# rev_1-_projecto.net
KiCad netlist of a schematic drawn in EasyEDA
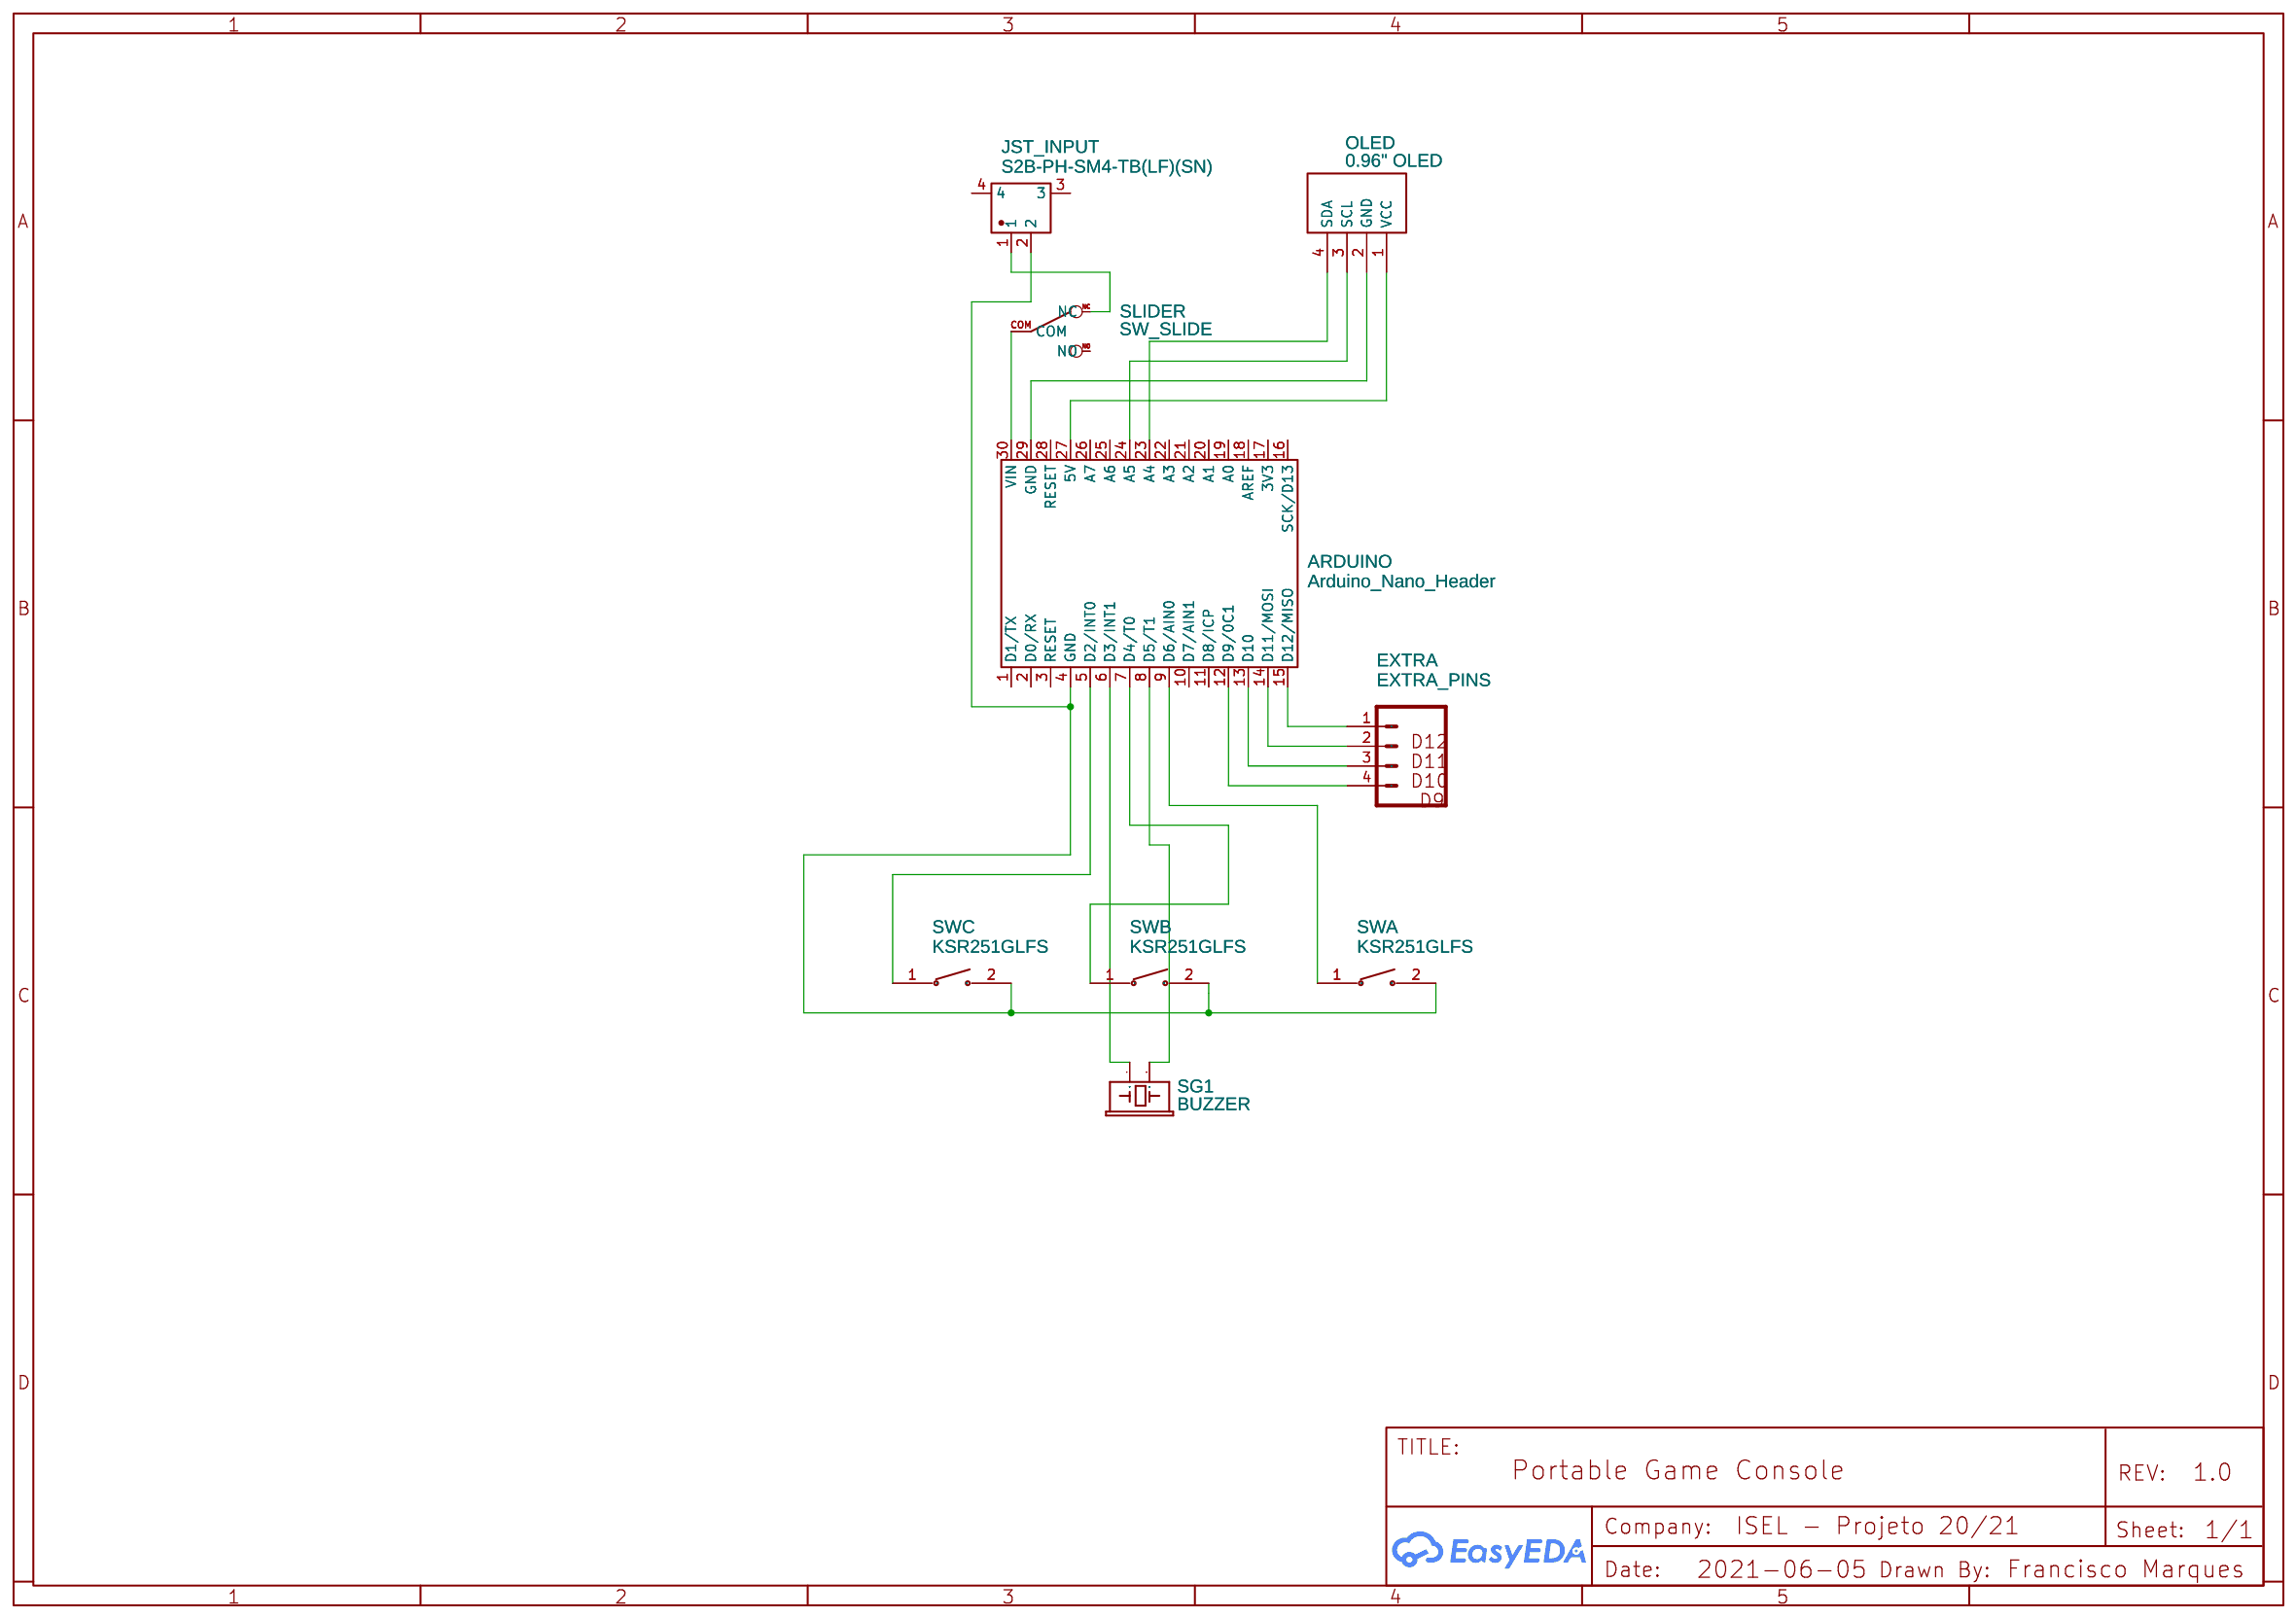
[diagram p0: schematic sheet]

(export (version "E")
  (design (tool "Eeschema 10.0.6"))
  (components
    (comp (ref "ARDUINO") (value "Arduino_Nano_Header") (libsource (lib "") (part "Arduino_Nano_Header")))
    (comp (ref "EXTRA") (value "EXTRA_PINS") (libsource (lib "") (part "EXTRA_PINS")))
    (comp (ref "JST_INPUT")
      (value "S2B-PH-SM4-TB(LF)(SN)")
      (fields (field (name "BOM_Supplier Part") "C295747"))
      (libsource (lib "") (part "S2B-PH-SM4-TB(LF)(SN)"))
    )
    (comp (ref "OLED") (value "0.96\" OLED") (libsource (lib "") (part "0.96{dblquote} OLED")))
    (comp (ref "SG1") (value "BUZZER") (libsource (lib "") (part "BUZZER")))
    (comp (ref "SLIDER") (value "SW_SLIDE") (libsource (lib "") (part "SW_SLIDE")))
    (comp (ref "SWA")
      (value "KSR251GLFS")
      (fields (field (name "BOM_Supplier Part") "C221790"))
      (libsource (lib "") (part "KSR251GLFS_2"))
    )
    (comp (ref "SWB")
      (value "KSR251GLFS")
      (fields (field (name "BOM_Supplier Part") "C221790"))
      (libsource (lib "") (part "KSR251GLFS_1"))
    )
    (comp (ref "SWC")
      (value "KSR251GLFS")
      (fields (field (name "BOM_Supplier Part") "C221790"))
      (libsource (lib "") (part "KSR251GLFS"))
    )
  )
  (nets
    (net (code "1") (name "Net-(ARDUINO-5V)") (class "Default")
      (node (ref "ARDUINO") (pin "27") (pinfunction "5V_27") (pintype "unspecified"))
      (node (ref "OLED") (pin "1") (pinfunction "VCC_1") (pintype "unspecified"))
    )
    (net (code "2") (name "Net-(ARDUINO-A4)") (class "Default")
      (node (ref "ARDUINO") (pin "23") (pinfunction "A4_23") (pintype "unspecified"))
      (node (ref "OLED") (pin "4") (pinfunction "SDA_4") (pintype "unspecified"))
    )
    (net (code "3") (name "Net-(ARDUINO-A5)") (class "Default")
      (node (ref "ARDUINO") (pin "24") (pinfunction "A5_24") (pintype "unspecified"))
      (node (ref "OLED") (pin "3") (pinfunction "SCL_3") (pintype "unspecified"))
    )
    (net (code "4") (name "Net-(ARDUINO-D2{slash}INT0)") (class "Default")
      (node (ref "ARDUINO") (pin "5") (pinfunction "D2/INT0_5") (pintype "unspecified"))
      (node (ref "SWC") (pin "1") (pinfunction "1_1") (pintype "unspecified"))
    )
    (net (code "5") (name "Net-(ARDUINO-D3{slash}INT1)") (class "Default")
      (node (ref "ARDUINO") (pin "6") (pinfunction "D3/INT1_6") (pintype "unspecified"))
      (node (ref "SG1") (pin "-") (pinfunction "2_-") (pintype "unspecified"))
    )
    (net (code "6") (name "Net-(ARDUINO-D4{slash}T0)") (class "Default")
      (node (ref "ARDUINO") (pin "7") (pinfunction "D4/T0_7") (pintype "unspecified"))
      (node (ref "SWB") (pin "1") (pinfunction "1_1") (pintype "unspecified"))
    )
    (net (code "7") (name "Net-(ARDUINO-D5{slash}T1)") (class "Default")
      (node (ref "ARDUINO") (pin "8") (pinfunction "D5/T1_8") (pintype "unspecified"))
      (node (ref "SG1") (pin "+") (pinfunction "1_+") (pintype "unspecified"))
    )
    (net (code "8") (name "Net-(ARDUINO-D6{slash}AIN0)") (class "Default")
      (node (ref "ARDUINO") (pin "9") (pinfunction "D6/AIN0_9") (pintype "unspecified"))
      (node (ref "SWA") (pin "1") (pinfunction "1_1") (pintype "unspecified"))
    )
    (net (code "9") (name "Net-(ARDUINO-D9{slash}0C1)") (class "Default")
      (node (ref "ARDUINO") (pin "12") (pinfunction "D9/0C1_12") (pintype "unspecified"))
      (node (ref "EXTRA") (pin "4") (pinfunction "4_4") (pintype "unspecified"))
    )
    (net (code "10") (name "Net-(ARDUINO-D10)") (class "Default")
      (node (ref "ARDUINO") (pin "13") (pinfunction "D10_13") (pintype "unspecified"))
      (node (ref "EXTRA") (pin "3") (pinfunction "3_3") (pintype "unspecified"))
    )
    (net (code "11") (name "Net-(ARDUINO-D11{slash}MOSI)") (class "Default")
      (node (ref "ARDUINO") (pin "14") (pinfunction "D11/MOSI_14") (pintype "unspecified"))
      (node (ref "EXTRA") (pin "2") (pinfunction "2_2") (pintype "unspecified"))
    )
    (net (code "12") (name "Net-(ARDUINO-D12{slash}MISO)") (class "Default")
      (node (ref "ARDUINO") (pin "15") (pinfunction "D12/MISO_15") (pintype "unspecified"))
      (node (ref "EXTRA") (pin "1") (pinfunction "1_1") (pintype "unspecified"))
    )
    (net (code "13") (name "Net-(ARDUINO-GND-Pad4)") (class "Default")
      (node (ref "ARDUINO") (pin "4") (pinfunction "GND_4") (pintype "unspecified"))
      (node (ref "JST_INPUT") (pin "2") (pinfunction "2_2") (pintype "unspecified"))
      (node (ref "SWA") (pin "2") (pinfunction "2_2") (pintype "unspecified"))
      (node (ref "SWB") (pin "2") (pinfunction "2_2") (pintype "unspecified"))
      (node (ref "SWC") (pin "2") (pinfunction "2_2") (pintype "unspecified"))
    )
    (net (code "14") (name "Net-(ARDUINO-VIN)") (class "Default")
      (node (ref "ARDUINO") (pin "30") (pinfunction "VIN_30") (pintype "unspecified"))
      (node (ref "SLIDER") (pin "COM") (pinfunction "COM_COM") (pintype "unspecified"))
    )
    (net (code "15") (name "Net-(JST_INPUT-Pad1)") (class "Default")
      (node (ref "JST_INPUT") (pin "1") (pinfunction "1_1") (pintype "unspecified"))
      (node (ref "SLIDER") (pin "NC") (pinfunction "NC_NC") (pintype "unspecified"))
    )
    (net (code "16") (name "Net-(OLED-GND)") (class "Default")
      (node (ref "ARDUINO") (pin "29") (pinfunction "GND_29") (pintype "unspecified"))
      (node (ref "OLED") (pin "2") (pinfunction "GND_2") (pintype "unspecified"))
    )
    (net (code "17") (name "unconnected-(ARDUINO-3V3-Pad17)") (class "Default")
      (node (ref "ARDUINO") (pin "17") (pinfunction "3V3_17") (pintype "unspecified"))
    )
    (net (code "18") (name "unconnected-(ARDUINO-A0-Pad19)") (class "Default")
      (node (ref "ARDUINO") (pin "19") (pinfunction "A0_19") (pintype "unspecified"))
    )
    (net (code "19") (name "unconnected-(ARDUINO-A1-Pad20)") (class "Default")
      (node (ref "ARDUINO") (pin "20") (pinfunction "A1_20") (pintype "unspecified"))
    )
    (net (code "20") (name "unconnected-(ARDUINO-A2-Pad21)") (class "Default")
      (node (ref "ARDUINO") (pin "21") (pinfunction "A2_21") (pintype "unspecified"))
    )
    (net (code "21") (name "unconnected-(ARDUINO-A3-Pad22)") (class "Default")
      (node (ref "ARDUINO") (pin "22") (pinfunction "A3_22") (pintype "unspecified"))
    )
    (net (code "22") (name "unconnected-(ARDUINO-A6-Pad25)") (class "Default")
      (node (ref "ARDUINO") (pin "25") (pinfunction "A6_25") (pintype "unspecified"))
    )
    (net (code "23") (name "unconnected-(ARDUINO-A7-Pad26)") (class "Default")
      (node (ref "ARDUINO") (pin "26") (pinfunction "A7_26") (pintype "unspecified"))
    )
    (net (code "24") (name "unconnected-(ARDUINO-AREF-Pad18)") (class "Default")
      (node (ref "ARDUINO") (pin "18") (pinfunction "AREF_18") (pintype "unspecified"))
    )
    (net (code "25") (name "unconnected-(ARDUINO-D0{slash}RX-Pad2)") (class "Default")
      (node (ref "ARDUINO") (pin "2") (pinfunction "D0/RX_2") (pintype "unspecified"))
    )
    (net (code "26") (name "unconnected-(ARDUINO-D1{slash}TX-Pad1)") (class "Default")
      (node (ref "ARDUINO") (pin "1") (pinfunction "D1/TX_1") (pintype "unspecified"))
    )
    (net (code "27") (name "unconnected-(ARDUINO-D7{slash}AIN1-Pad10)") (class "Default")
      (node (ref "ARDUINO") (pin "10") (pinfunction "D7/AIN1_10") (pintype "unspecified"))
    )
    (net (code "28") (name "unconnected-(ARDUINO-D8{slash}ICP-Pad11)") (class "Default")
      (node (ref "ARDUINO") (pin "11") (pinfunction "D8/ICP_11") (pintype "unspecified"))
    )
    (net (code "29") (name "unconnected-(ARDUINO-RESET-Pad3)") (class "Default")
      (node (ref "ARDUINO") (pin "3") (pinfunction "RESET_3") (pintype "unspecified"))
    )
    (net (code "30") (name "unconnected-(ARDUINO-RESET-Pad28)") (class "Default")
      (node (ref "ARDUINO") (pin "28") (pinfunction "RESET_28") (pintype "unspecified"))
    )
    (net (code "31") (name "unconnected-(ARDUINO-SCK{slash}D13-Pad16)") (class "Default")
      (node (ref "ARDUINO") (pin "16") (pinfunction "SCK/D13_16") (pintype "unspecified"))
    )
    (net (code "32") (name "unconnected-(JST_INPUT-Pad3)") (class "Default")
      (node (ref "JST_INPUT") (pin "3") (pinfunction "3_3") (pintype "unspecified"))
    )
    (net (code "33") (name "unconnected-(JST_INPUT-Pad4)") (class "Default")
      (node (ref "JST_INPUT") (pin "4") (pinfunction "4_4") (pintype "unspecified"))
    )
    (net (code "34") (name "unconnected-(SLIDER-PadNO)") (class "Default")
      (node (ref "SLIDER") (pin "NO") (pinfunction "NO_NO") (pintype "unspecified"))
    )
  )
)
